# SCH_fluffly_2_2024-03-27.net
KiCad netlist of a schematic drawn in EasyEDA
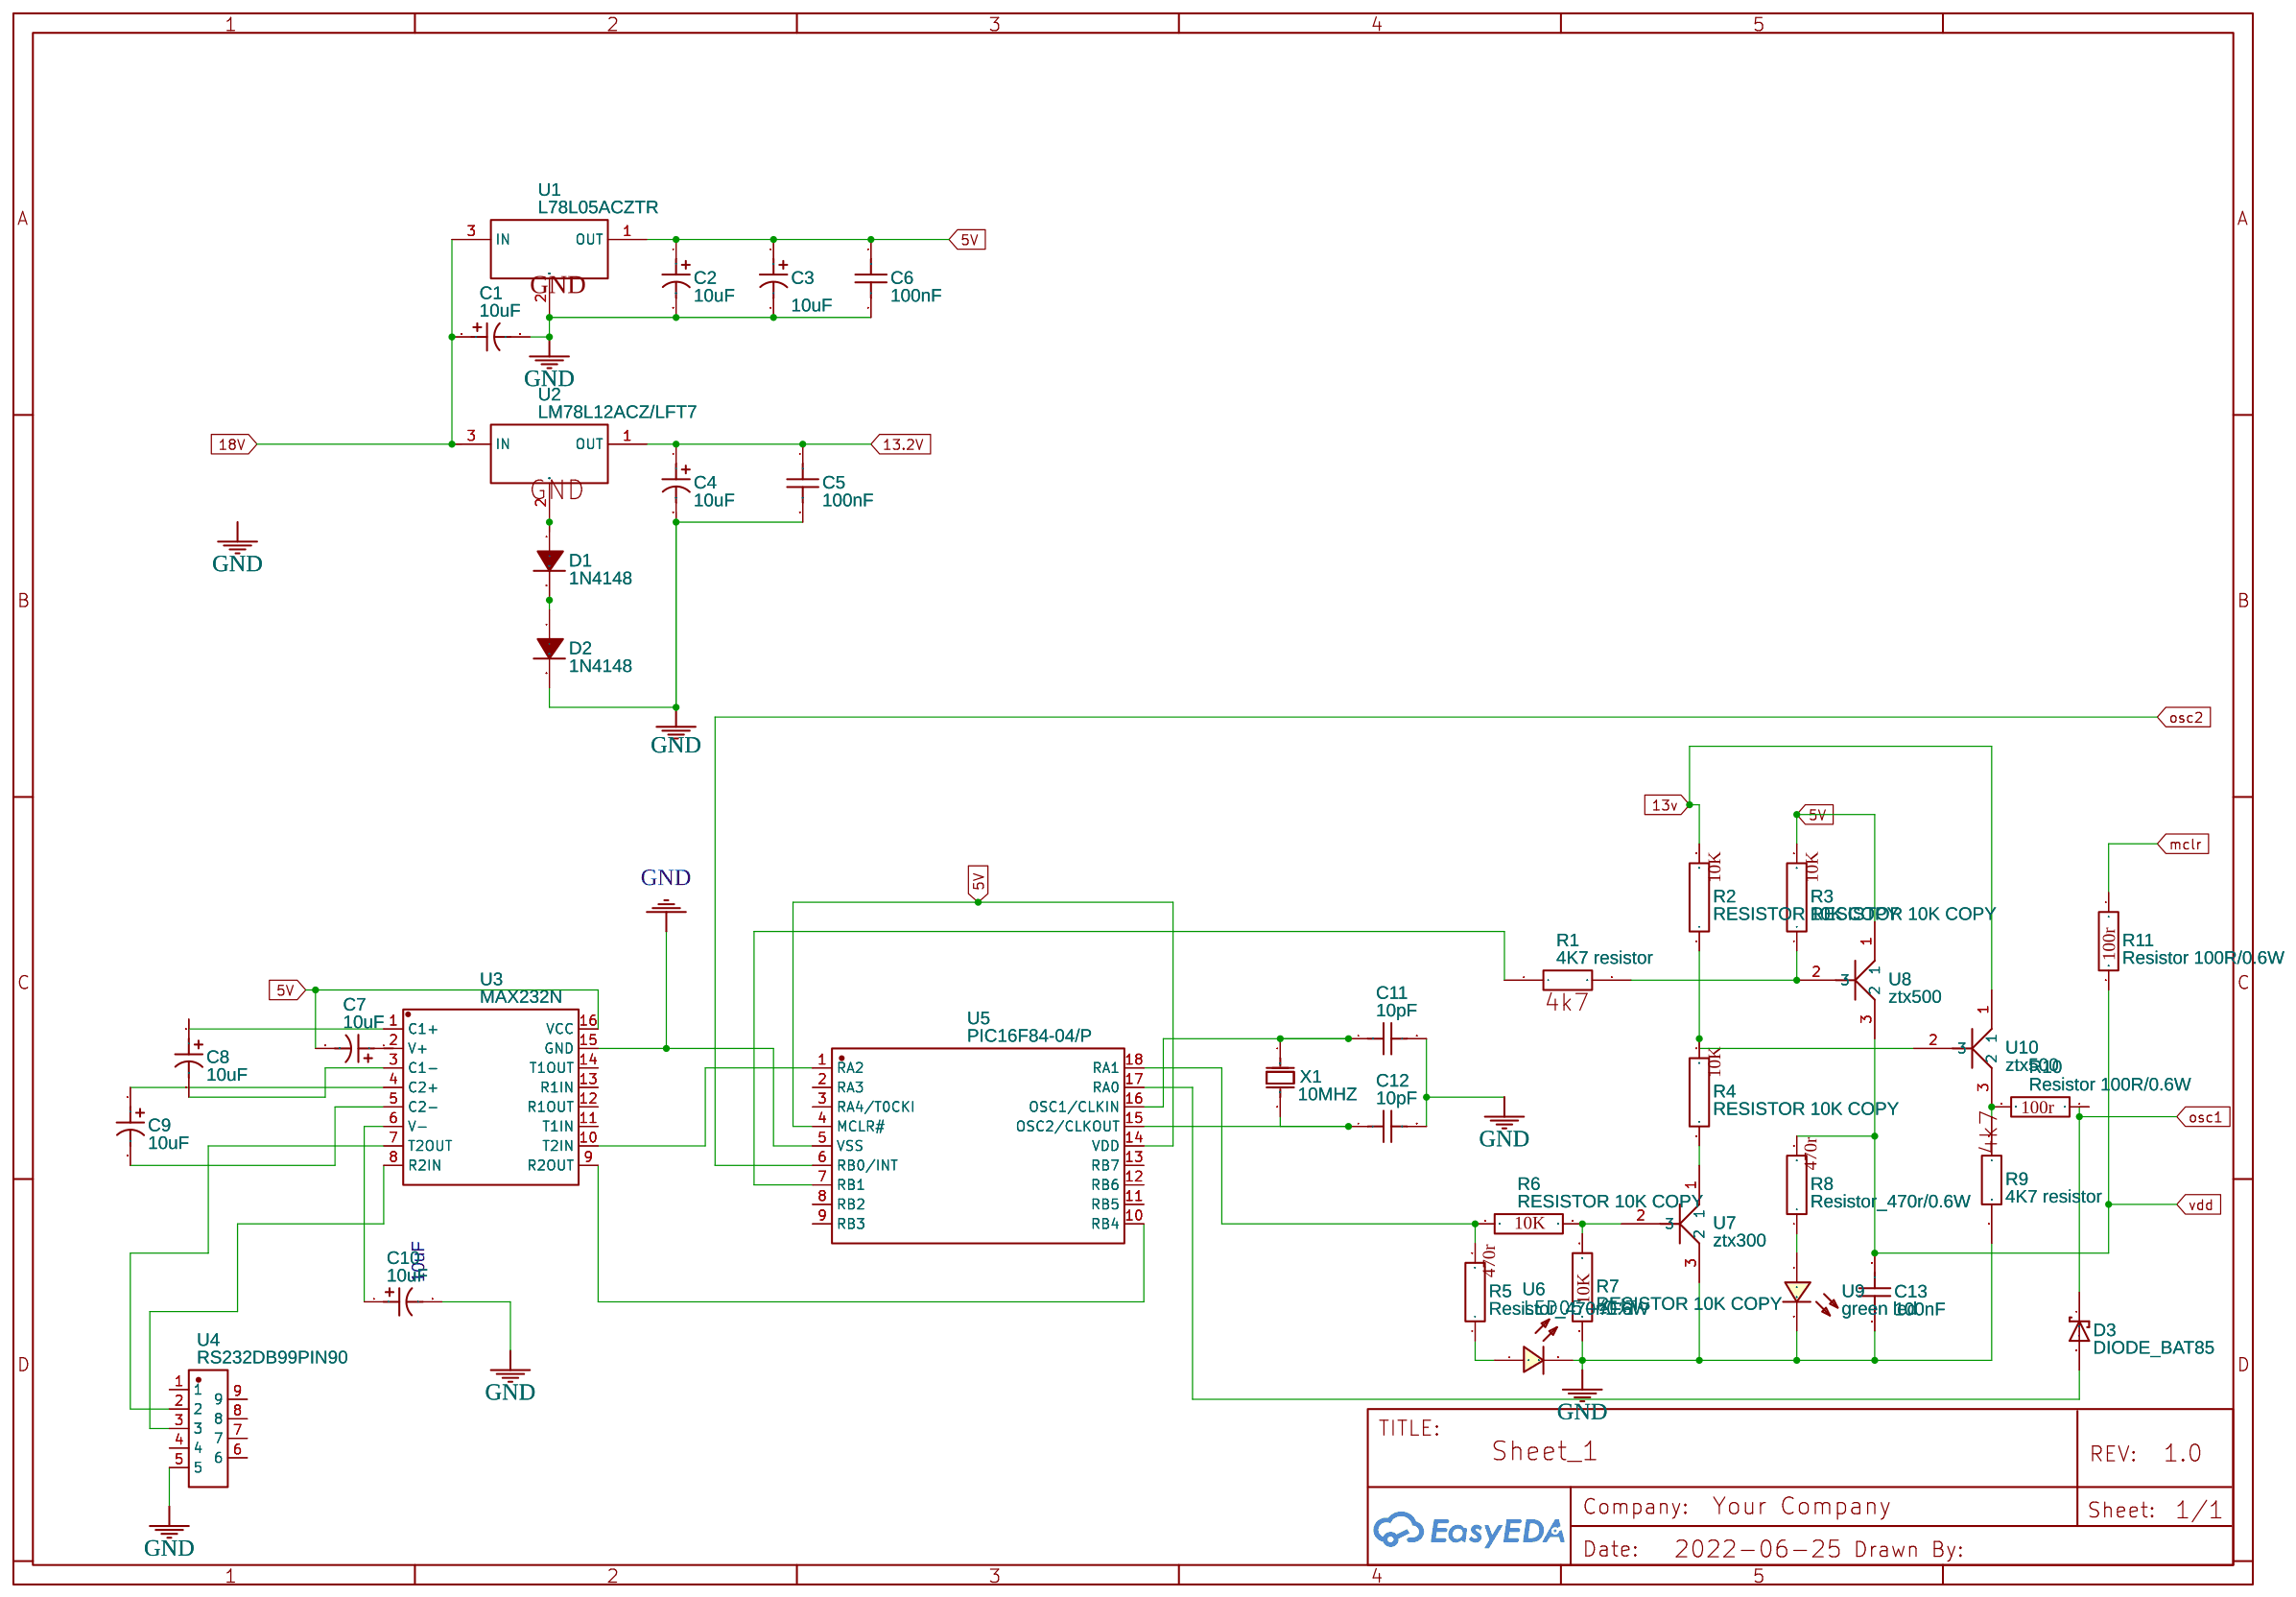
[diagram p0: schematic sheet]

(export (version "E")
  (design (tool "Eeschema 10.0.6"))
  (components
    (comp (ref "C1")
      (value "10uF")
      (fields (field (name "Manufacturer Part") "RFS-50V100MG3#") (field (name "Manufacturer") "ELNA(伊娜)"))
      (libsource (lib "") (part "RFS-50V100MG3#_4"))
    )
    (comp (ref "C2")
      (value "10uF")
      (fields (field (name "Manufacturer Part") "RFS-50V100MG3#") (field (name "Manufacturer") "ELNA(伊娜)"))
      (libsource (lib "") (part "RFS-50V100MG3#_1"))
    )
    (comp (ref "C3")
      (value "10uF")
      (fields (field (name "Manufacturer Part") "RFS-50V100MG3#") (field (name "Manufacturer") "ELNA(伊娜)"))
      (libsource (lib "") (part "RFS-50V100MG3#_1"))
    )
    (comp (ref "C4")
      (value "10uF")
      (fields (field (name "Manufacturer Part") "RFS-50V100MG3#") (field (name "Manufacturer") "ELNA(伊娜)"))
      (libsource (lib "") (part "RFS-50V100MG3#_1"))
    )
    (comp (ref "C5")
      (value "100nF")
      (fields
        (field (name "Manufacturer Part") "DCS104Z26Y5VF58L5A0")
        (field (name "Manufacturer") "SHM(南方宏明)")
      )
      (libsource (lib "") (part "DCS104Z26Y5VF58L5A0"))
    )
    (comp (ref "C6")
      (value "100nF")
      (fields
        (field (name "Manufacturer Part") "DCS104Z26Y5VF58L5A0")
        (field (name "Manufacturer") "SHM(南方宏明)")
      )
      (libsource (lib "") (part "DCS104Z26Y5VF58L5A0"))
    )
    (comp (ref "C7")
      (value "10uF")
      (fields (field (name "Manufacturer Part") "RFS-50V100MG3#") (field (name "Manufacturer") "ELNA(伊娜)"))
      (libsource (lib "") (part "RFS-50V100MG3#"))
    )
    (comp (ref "C8")
      (value "10uF")
      (fields (field (name "Manufacturer Part") "RFS-50V100MG3#") (field (name "Manufacturer") "ELNA(伊娜)"))
      (libsource (lib "") (part "RFS-50V100MG3#_2"))
    )
    (comp (ref "C9")
      (value "10uF")
      (fields (field (name "Manufacturer Part") "RFS-50V100MG3#") (field (name "Manufacturer") "ELNA(伊娜)"))
      (libsource (lib "") (part "RFS-50V100MG3#_1"))
    )
    (comp (ref "C10")
      (value "10uF")
      (fields (field (name "Manufacturer Part") "RFS-50V100MG3#") (field (name "Manufacturer") "ELNA(伊娜)"))
      (libsource (lib "") (part "RFS-50V100MG3#_3"))
    )
    (comp (ref "C11")
      (value "10pF")
      (fields (field (name "Manufacturer Part") "CC45SL3FD100JYNNA") (field (name "Manufacturer") "TDK"))
      (libsource (lib "") (part "CC45SL3FD100JYNNA"))
    )
    (comp (ref "C12")
      (value "10pF")
      (fields (field (name "Manufacturer Part") "CC45SL3FD100JYNNA") (field (name "Manufacturer") "TDK"))
      (libsource (lib "") (part "CC45SL3FD100JYNNA"))
    )
    (comp (ref "C13")
      (value "100nF")
      (fields
        (field (name "Manufacturer Part") "DCS104Z26Y5VF58L5A0")
        (field (name "Manufacturer") "SHM(南方宏明)")
      )
      (libsource (lib "") (part "DCS104Z26Y5VF58L5A0"))
    )
    (comp (ref "D1")
      (value "1N4148")
      (fields (field (name "Manufacturer") "SEMTECH"))
      (libsource (lib "") (part "1N4148"))
    )
    (comp (ref "D2")
      (value "1N4148")
      (fields (field (name "Manufacturer") "SEMTECH"))
      (libsource (lib "") (part "1N4148"))
    )
    (comp (ref "D3") (value "DIODE_BAT85") (libsource (lib "") (part "DIODE_BAT85")))
    (comp (ref "R1") (value "4K7 resistor") (libsource (lib "") (part "4K7 resistor")))
    (comp (ref "R2") (value "RESISTOR 10K COPY") (libsource (lib "") (part "RESISTOR 10K COPY")))
    (comp (ref "R3") (value "RESISTOR 10K COPY") (libsource (lib "") (part "RESISTOR 10K COPY")))
    (comp (ref "R4") (value "RESISTOR 10K COPY") (libsource (lib "") (part "RESISTOR 10K COPY")))
    (comp (ref "R5") (value "Resistor_470r/0.6W") (libsource (lib "") (part "Resistor_470r/0.6W")))
    (comp (ref "R6") (value "RESISTOR 10K COPY") (libsource (lib "") (part "RESISTOR 10K COPY_2")))
    (comp (ref "R7") (value "RESISTOR 10K COPY") (libsource (lib "") (part "RESISTOR 10K COPY_1")))
    (comp (ref "R8") (value "Resistor_470r/0.6W") (libsource (lib "") (part "Resistor_470r/0.6W")))
    (comp (ref "R9") (value "4K7 resistor") (libsource (lib "") (part "4K7 resistor_1")))
    (comp (ref "R10") (value "Resistor 100R/0.6W") (libsource (lib "") (part "Resistor 100R/0.6W")))
    (comp (ref "R11") (value "Resistor 100R/0.6W") (libsource (lib "") (part "Resistor 100R/0.6W_1")))
    (comp (ref "U1")
      (value "L78L05ACZTR")
      (fields (field (name "Manufacturer") "STMicroelectronics"))
      (libsource (lib "") (part "L78L05ACZTR"))
    )
    (comp (ref "U2")
      (value "LM78L12ACZ/LFT7")
      (fields (field (name "Manufacturer") "TI(德州仪器)"))
      (libsource (lib "") (part "LM78L12ACZ/LFT7"))
    )
    (comp (ref "U3")
      (value "MAX232N")
      (fields (field (name "Manufacturer") "Texas Instruments"))
      (libsource (lib "") (part "MAX232N"))
    )
    (comp (ref "U4")
      (value "RS232DB99PIN90")
      (fields (field (name "Manufacturer Part") "RS232DB99pin90度母座"))
      (libsource (lib "") (part "RS232DB99PIN90"))
    )
    (comp (ref "U5")
      (value "PIC16F84-04/P")
      (fields (field (name "Manufacturer") "Microchip Tech"))
      (libsource (lib "") (part "PIC16F84-04/P"))
    )
    (comp (ref "U6") (value "LED05-红灯") (libsource (lib "") (part "LED05-红灯")))
    (comp (ref "U7") (value "ztx300") (libsource (lib "") (part "transistor")))
    (comp (ref "U8") (value "ztx500") (libsource (lib "") (part "transistor")))
    (comp (ref "U9")
      (value "green led")
      (fields (field (name "Manufacturer Part") "LED05-红灯"))
      (libsource (lib "") (part "LED05-红灯_1"))
    )
    (comp (ref "U10") (value "ztx500") (libsource (lib "") (part "transistor")))
    (comp (ref "X1")
      (value "10MHZ")
      (fields (field (name "Manufacturer Part") "509-0400A2020-00") (field (name "Manufacturer") "XTY"))
      (libsource (lib "") (part "509-0400A2020-00"))
    )
  )
  (nets
    (net (code "1") (name "5V") (class "Default")
      (node (ref "C2") (pin "1") (pinfunction "1_1") (pintype "input"))
      (node (ref "C3") (pin "1") (pinfunction "1_1") (pintype "input"))
      (node (ref "C6") (pin "1") (pinfunction "1_1") (pintype "unspecified"))
      (node (ref "C7") (pin "2") (pinfunction "2_2") (pintype "input"))
      (node (ref "R3") (pin "2") (pinfunction "2_2") (pintype "unspecified"))
      (node (ref "U1") (pin "1") (pinfunction "OUT_1") (pintype "passive"))
      (node (ref "U3") (pin "16") (pinfunction "VCC_16") (pintype "unspecified"))
      (node (ref "U5") (pin "14") (pinfunction "VDD_14") (pintype "unspecified"))
      (node (ref "U5") (pin "4") (pinfunction "MCLR#_4") (pintype "unspecified"))
      (node (ref "U8") (pin "1") (pinfunction "1_1") (pintype "unspecified"))
    )
    (net (code "2") (name "13.2V") (class "Default")
      (node (ref "C4") (pin "1") (pinfunction "1_1") (pintype "input"))
      (node (ref "C5") (pin "1") (pinfunction "1_1") (pintype "unspecified"))
      (node (ref "U2") (pin "1") (pinfunction "OUT_1") (pintype "passive"))
    )
    (net (code "3") (name "13v") (class "Default")
      (node (ref "R2") (pin "2") (pinfunction "2_2") (pintype "unspecified"))
      (node (ref "U10") (pin "1") (pinfunction "1_1") (pintype "unspecified"))
    )
    (net (code "4") (name "18V") (class "Default")
      (node (ref "C1") (pin "1") (pinfunction "1_1") (pintype "input"))
      (node (ref "U1") (pin "3") (pinfunction "IN_3") (pintype "passive"))
      (node (ref "U2") (pin "3") (pinfunction "IN_3") (pintype "passive"))
    )
    (net (code "5") (name "GND") (class "Default")
      (node (ref "C1") (pin "2") (pinfunction "2_2") (pintype "input"))
      (node (ref "C10") (pin "2") (pinfunction "2_2") (pintype "input"))
      (node (ref "C11") (pin "2") (pinfunction "2_2") (pintype "unspecified"))
      (node (ref "C12") (pin "2") (pinfunction "2_2") (pintype "unspecified"))
      (node (ref "C13") (pin "2") (pinfunction "2_2") (pintype "unspecified"))
      (node (ref "C2") (pin "2") (pinfunction "2_2") (pintype "input"))
      (node (ref "C3") (pin "2") (pinfunction "2_2") (pintype "input"))
      (node (ref "C4") (pin "2") (pinfunction "2_2") (pintype "input"))
      (node (ref "C5") (pin "2") (pinfunction "2_2") (pintype "unspecified"))
      (node (ref "C6") (pin "2") (pinfunction "2_2") (pintype "unspecified"))
      (node (ref "D2") (pin "2") (pinfunction "C_2") (pintype "unspecified"))
      (node (ref "R7") (pin "1") (pinfunction "1_1") (pintype "unspecified"))
      (node (ref "R9") (pin "2") (pinfunction "2_2") (pintype "unspecified"))
      (node (ref "U1") (pin "2") (pinfunction "GND_2") (pintype "passive"))
      (node (ref "U3") (pin "15") (pinfunction "GND_15") (pintype "unspecified"))
      (node (ref "U4") (pin "5") (pinfunction "5_5") (pintype "unspecified"))
      (node (ref "U5") (pin "5") (pinfunction "VSS_5") (pintype "unspecified"))
      (node (ref "U6") (pin "2") (pinfunction "2_2") (pintype "unspecified"))
      (node (ref "U7") (pin "3") (pinfunction "2_3") (pintype "unspecified"))
      (node (ref "U9") (pin "2") (pinfunction "2_2") (pintype "unspecified"))
    )
    (net (code "6") (name "Net-(D1-A)") (class "Default")
      (node (ref "D1") (pin "1") (pinfunction "A_1") (pintype "unspecified"))
      (node (ref "U2") (pin "2") (pinfunction "GND_2") (pintype "passive"))
    )
    (net (code "7") (name "Net-(D1-C)") (class "Default")
      (node (ref "D1") (pin "2") (pinfunction "C_2") (pintype "unspecified"))
      (node (ref "D2") (pin "1") (pinfunction "A_1") (pintype "unspecified"))
    )
    (net (code "8") (name "Net-(D3-A)") (class "Default")
      (node (ref "D3") (pin "2") (pinfunction "A_2") (pintype "unspecified"))
      (node (ref "U5") (pin "17") (pinfunction "RA0_17") (pintype "unspecified"))
    )
    (net (code "9") (name "Net-(R4-Pad1)") (class "Default")
      (node (ref "R4") (pin "1") (pinfunction "1_1") (pintype "unspecified"))
      (node (ref "U7") (pin "1") (pinfunction "1_1") (pintype "unspecified"))
    )
    (net (code "10") (name "Net-(R5-Pad1)") (class "Default")
      (node (ref "R5") (pin "1") (pinfunction "1_1") (pintype "unspecified"))
      (node (ref "U6") (pin "1") (pinfunction "1_1") (pintype "unspecified"))
    )
    (net (code "11") (name "Net-(R8-Pad1)") (class "Default")
      (node (ref "R8") (pin "1") (pinfunction "1_1") (pintype "unspecified"))
      (node (ref "U9") (pin "1") (pinfunction "1_1") (pintype "unspecified"))
    )
    (net (code "12") (name "Net-(U3-C1+)") (class "Default")
      (node (ref "C8") (pin "1") (pinfunction "1_1") (pintype "input"))
      (node (ref "U3") (pin "1") (pinfunction "C1+_1") (pintype "unspecified"))
    )
    (net (code "13") (name "Net-(U3-C1-)") (class "Default")
      (node (ref "C8") (pin "2") (pinfunction "2_2") (pintype "input"))
      (node (ref "U3") (pin "3") (pinfunction "C1-_3") (pintype "unspecified"))
    )
    (net (code "14") (name "Net-(U3-C2+)") (class "Default")
      (node (ref "C9") (pin "1") (pinfunction "1_1") (pintype "input"))
      (node (ref "U3") (pin "4") (pinfunction "C2+_4") (pintype "unspecified"))
    )
    (net (code "15") (name "Net-(U3-C2-)") (class "Default")
      (node (ref "C9") (pin "2") (pinfunction "2_2") (pintype "input"))
      (node (ref "U3") (pin "5") (pinfunction "C2-_5") (pintype "unspecified"))
    )
    (net (code "16") (name "Net-(U3-R2IN)") (class "Default")
      (node (ref "U3") (pin "8") (pinfunction "R2IN_8") (pintype "unspecified"))
      (node (ref "U4") (pin "3") (pinfunction "3_3") (pintype "unspecified"))
    )
    (net (code "17") (name "Net-(U3-R2OUT)") (class "Default")
      (node (ref "U3") (pin "9") (pinfunction "R2OUT_9") (pintype "unspecified"))
      (node (ref "U5") (pin "10") (pinfunction "RB4_10") (pintype "unspecified"))
    )
    (net (code "18") (name "Net-(U3-T2IN)") (class "Default")
      (node (ref "U3") (pin "10") (pinfunction "T2IN_10") (pintype "unspecified"))
      (node (ref "U5") (pin "1") (pinfunction "RA2_1") (pintype "unspecified"))
    )
    (net (code "19") (name "Net-(U3-T2OUT)") (class "Default")
      (node (ref "U3") (pin "7") (pinfunction "T2OUT_7") (pintype "unspecified"))
      (node (ref "U4") (pin "2") (pinfunction "2_2") (pintype "unspecified"))
    )
    (net (code "20") (name "Net-(U3-V+)") (class "Default")
      (node (ref "C7") (pin "1") (pinfunction "1_1") (pintype "input"))
      (node (ref "U3") (pin "2") (pinfunction "V+_2") (pintype "unspecified"))
    )
    (net (code "21") (name "Net-(U3-V-)") (class "Default")
      (node (ref "C10") (pin "1") (pinfunction "1_1") (pintype "input"))
      (node (ref "U3") (pin "6") (pinfunction "V-_6") (pintype "unspecified"))
    )
    (net (code "22") (name "Net-(U5-OSC1{slash}CLKIN)") (class "Default")
      (node (ref "C11") (pin "1") (pinfunction "1_1") (pintype "unspecified"))
      (node (ref "U5") (pin "16") (pinfunction "OSC1/CLKIN_16") (pintype "unspecified"))
      (node (ref "X1") (pin "1") (pinfunction "OSC1_1") (pintype "input"))
    )
    (net (code "23") (name "Net-(U5-OSC2{slash}CLKOUT)") (class "Default")
      (node (ref "C12") (pin "1") (pinfunction "1_1") (pintype "unspecified"))
      (node (ref "U5") (pin "15") (pinfunction "OSC2/CLKOUT_15") (pintype "unspecified"))
      (node (ref "X1") (pin "2") (pinfunction "OSC2_2") (pintype "input"))
    )
    (net (code "24") (name "Net-(U5-RA1)") (class "Default")
      (node (ref "R5") (pin "2") (pinfunction "2_2") (pintype "unspecified"))
      (node (ref "R6") (pin "2") (pinfunction "2_2") (pintype "unspecified"))
      (node (ref "U5") (pin "18") (pinfunction "RA1_18") (pintype "unspecified"))
    )
    (net (code "25") (name "Net-(U5-RB1)") (class "Default")
      (node (ref "R1") (pin "1") (pinfunction "1_1") (pintype "unspecified"))
      (node (ref "U5") (pin "7") (pinfunction "RB1_7") (pintype "unspecified"))
    )
    (net (code "26") (name "Net-(U7-3)") (class "Default")
      (node (ref "R6") (pin "1") (pinfunction "1_1") (pintype "unspecified"))
      (node (ref "R7") (pin "2") (pinfunction "2_2") (pintype "unspecified"))
      (node (ref "U7") (pin "2") (pinfunction "3_2") (pintype "unspecified"))
    )
    (net (code "27") (name "Net-(U8-3)") (class "Default")
      (node (ref "R1") (pin "2") (pinfunction "2_2") (pintype "unspecified"))
      (node (ref "R3") (pin "1") (pinfunction "1_1") (pintype "unspecified"))
      (node (ref "U8") (pin "2") (pinfunction "3_2") (pintype "unspecified"))
    )
    (net (code "28") (name "Net-(U10-2)") (class "Default")
      (node (ref "R10") (pin "2") (pinfunction "2_2") (pintype "unspecified"))
      (node (ref "R9") (pin "1") (pinfunction "1_1") (pintype "unspecified"))
      (node (ref "U10") (pin "3") (pinfunction "2_3") (pintype "unspecified"))
    )
    (net (code "29") (name "Net-(U10-3)") (class "Default")
      (node (ref "R2") (pin "1") (pinfunction "1_1") (pintype "unspecified"))
      (node (ref "R4") (pin "2") (pinfunction "2_2") (pintype "unspecified"))
      (node (ref "U10") (pin "2") (pinfunction "3_2") (pintype "unspecified"))
    )
    (net (code "30") (name "mclr") (class "Default")
      (node (ref "R11") (pin "1") (pinfunction "1_1") (pintype "unspecified"))
    )
    (net (code "31") (name "osc1") (class "Default")
      (node (ref "D3") (pin "1") (pinfunction "K_1") (pintype "unspecified"))
      (node (ref "R10") (pin "1") (pinfunction "1_1") (pintype "unspecified"))
    )
    (net (code "32") (name "osc2") (class "Default")
      (node (ref "U5") (pin "6") (pinfunction "RB0/INT_6") (pintype "unspecified"))
    )
    (net (code "33") (name "unconnected-(U3-R1IN-Pad13)") (class "Default")
      (node (ref "U3") (pin "13") (pinfunction "R1IN_13") (pintype "unspecified"))
    )
    (net (code "34") (name "unconnected-(U3-R1OUT-Pad12)") (class "Default")
      (node (ref "U3") (pin "12") (pinfunction "R1OUT_12") (pintype "unspecified"))
    )
    (net (code "35") (name "unconnected-(U3-T1IN-Pad11)") (class "Default")
      (node (ref "U3") (pin "11") (pinfunction "T1IN_11") (pintype "unspecified"))
    )
    (net (code "36") (name "unconnected-(U3-T1OUT-Pad14)") (class "Default")
      (node (ref "U3") (pin "14") (pinfunction "T1OUT_14") (pintype "unspecified"))
    )
    (net (code "37") (name "unconnected-(U4-Pad1)") (class "Default")
      (node (ref "U4") (pin "1") (pinfunction "1_1") (pintype "unspecified"))
    )
    (net (code "38") (name "unconnected-(U4-Pad4)") (class "Default")
      (node (ref "U4") (pin "4") (pinfunction "4_4") (pintype "unspecified"))
    )
    (net (code "39") (name "unconnected-(U4-Pad6)") (class "Default")
      (node (ref "U4") (pin "6") (pinfunction "6_6") (pintype "unspecified"))
    )
    (net (code "40") (name "unconnected-(U4-Pad7)") (class "Default")
      (node (ref "U4") (pin "7") (pinfunction "7_7") (pintype "unspecified"))
    )
    (net (code "41") (name "unconnected-(U4-Pad8)") (class "Default")
      (node (ref "U4") (pin "8") (pinfunction "8_8") (pintype "unspecified"))
    )
    (net (code "42") (name "unconnected-(U4-Pad9)") (class "Default")
      (node (ref "U4") (pin "9") (pinfunction "9_9") (pintype "unspecified"))
    )
    (net (code "43") (name "unconnected-(U5-RA3-Pad2)") (class "Default")
      (node (ref "U5") (pin "2") (pinfunction "RA3_2") (pintype "unspecified"))
    )
    (net (code "44") (name "unconnected-(U5-RA4{slash}T0CKI-Pad3)") (class "Default")
      (node (ref "U5") (pin "3") (pinfunction "RA4/T0CKI_3") (pintype "unspecified"))
    )
    (net (code "45") (name "unconnected-(U5-RB2-Pad8)") (class "Default")
      (node (ref "U5") (pin "8") (pinfunction "RB2_8") (pintype "unspecified"))
    )
    (net (code "46") (name "unconnected-(U5-RB3-Pad9)") (class "Default")
      (node (ref "U5") (pin "9") (pinfunction "RB3_9") (pintype "unspecified"))
    )
    (net (code "47") (name "unconnected-(U5-RB5-Pad11)") (class "Default")
      (node (ref "U5") (pin "11") (pinfunction "RB5_11") (pintype "unspecified"))
    )
    (net (code "48") (name "unconnected-(U5-RB6-Pad12)") (class "Default")
      (node (ref "U5") (pin "12") (pinfunction "RB6_12") (pintype "unspecified"))
    )
    (net (code "49") (name "unconnected-(U5-RB7-Pad13)") (class "Default")
      (node (ref "U5") (pin "13") (pinfunction "RB7_13") (pintype "unspecified"))
    )
    (net (code "50") (name "vdd") (class "Default")
      (node (ref "C13") (pin "1") (pinfunction "1_1") (pintype "unspecified"))
      (node (ref "R11") (pin "2") (pinfunction "2_2") (pintype "unspecified"))
      (node (ref "R8") (pin "2") (pinfunction "2_2") (pintype "unspecified"))
      (node (ref "U8") (pin "3") (pinfunction "2_3") (pintype "unspecified"))
    )
  )
)
